# balconyDreams.net
KiCad netlist of a schematic drawn in EAGLE
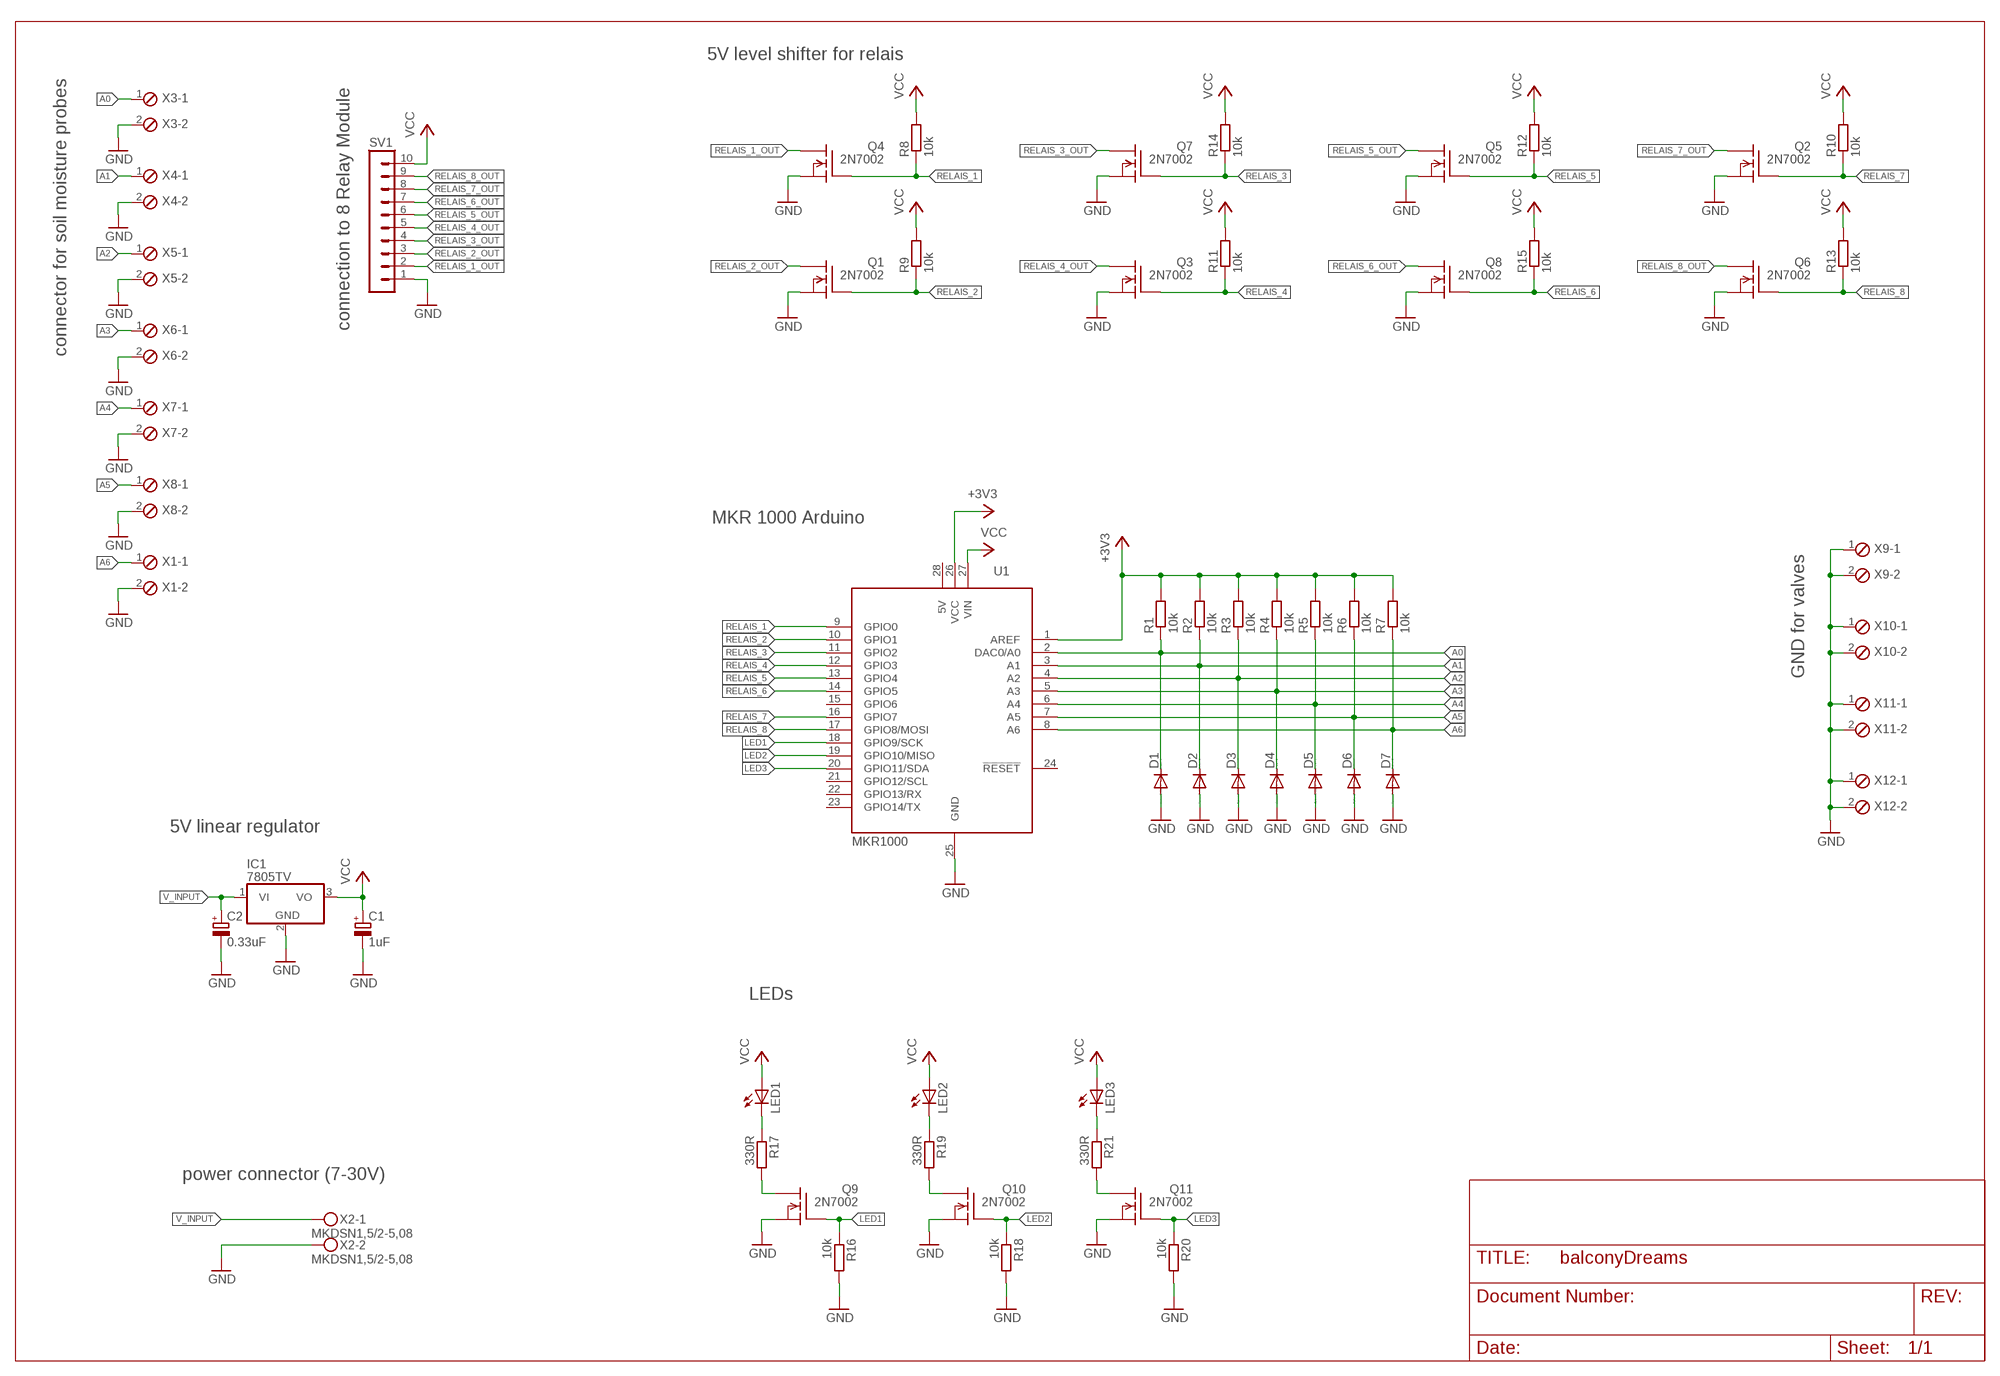
[diagram p0: schematic, sheet 1]

(export (version "E")
  (design (tool "Eeschema 10.0.6"))
  (components
    (comp (ref "C1")
      (value "1uF")
      (footprint "eagle-import:E5-6")
      (libsource (lib "eagle-import") (part "CPOL-EUE5-6"))
    )
    (comp (ref "C2")
      (value "0.33uF")
      (footprint "eagle-import:E5-6")
      (libsource (lib "eagle-import") (part "CPOL-EUE5-6"))
    )
    (comp (ref "D1")
      (value "DIODE-SOD323-W")
      (footprint "eagle-import:SOD323-W")
      (libsource (lib "eagle-import") (part "DIODE-SOD323-W"))
    )
    (comp (ref "D2")
      (value "DIODE-SOD323-W")
      (footprint "eagle-import:SOD323-W")
      (libsource (lib "eagle-import") (part "DIODE-SOD323-W"))
    )
    (comp (ref "D3")
      (value "DIODE-SOD323-W")
      (footprint "eagle-import:SOD323-W")
      (libsource (lib "eagle-import") (part "DIODE-SOD323-W"))
    )
    (comp (ref "D4")
      (value "DIODE-SOD323-W")
      (footprint "eagle-import:SOD323-W")
      (libsource (lib "eagle-import") (part "DIODE-SOD323-W"))
    )
    (comp (ref "D5")
      (value "DIODE-SOD323-W")
      (footprint "eagle-import:SOD323-W")
      (libsource (lib "eagle-import") (part "DIODE-SOD323-W"))
    )
    (comp (ref "D6")
      (value "DIODE-SOD323-W")
      (footprint "eagle-import:SOD323-W")
      (libsource (lib "eagle-import") (part "DIODE-SOD323-W"))
    )
    (comp (ref "D7")
      (value "DIODE-SOD323-W")
      (footprint "eagle-import:SOD323-W")
      (libsource (lib "eagle-import") (part "DIODE-SOD323-W"))
    )
    (comp (ref "IC1")
      (value "7805TV")
      (footprint "eagle-import:TO220V")
      (libsource (lib "eagle-import") (part "78TV05"))
    )
    (comp (ref "LED1")
      (value "LEDCHIPLED_0805")
      (footprint "eagle-import:CHIPLED_0805")
      (libsource (lib "eagle-import") (part "LEDCHIPLED_0805"))
    )
    (comp (ref "LED2")
      (value "LEDCHIPLED_0805")
      (footprint "eagle-import:CHIPLED_0805")
      (libsource (lib "eagle-import") (part "LEDCHIPLED_0805"))
    )
    (comp (ref "LED3")
      (value "LEDCHIPLED_0805")
      (footprint "eagle-import:CHIPLED_0805")
      (libsource (lib "eagle-import") (part "LEDCHIPLED_0805"))
    )
    (comp (ref "Q1")
      (value "2N7002")
      (footprint "eagle-import:SOT23")
      (libsource (lib "eagle-import") (part "2N7002"))
    )
    (comp (ref "Q2")
      (value "2N7002")
      (footprint "eagle-import:SOT23")
      (libsource (lib "eagle-import") (part "2N7002"))
    )
    (comp (ref "Q3")
      (value "2N7002")
      (footprint "eagle-import:SOT23")
      (libsource (lib "eagle-import") (part "2N7002"))
    )
    (comp (ref "Q4")
      (value "2N7002")
      (footprint "eagle-import:SOT23")
      (libsource (lib "eagle-import") (part "2N7002"))
    )
    (comp (ref "Q5")
      (value "2N7002")
      (footprint "eagle-import:SOT23")
      (libsource (lib "eagle-import") (part "2N7002"))
    )
    (comp (ref "Q6")
      (value "2N7002")
      (footprint "eagle-import:SOT23")
      (libsource (lib "eagle-import") (part "2N7002"))
    )
    (comp (ref "Q7")
      (value "2N7002")
      (footprint "eagle-import:SOT23")
      (libsource (lib "eagle-import") (part "2N7002"))
    )
    (comp (ref "Q8")
      (value "2N7002")
      (footprint "eagle-import:SOT23")
      (libsource (lib "eagle-import") (part "2N7002"))
    )
    (comp (ref "Q9")
      (value "2N7002")
      (footprint "eagle-import:SOT23")
      (libsource (lib "eagle-import") (part "2N7002"))
    )
    (comp (ref "Q10")
      (value "2N7002")
      (footprint "eagle-import:SOT23")
      (libsource (lib "eagle-import") (part "2N7002"))
    )
    (comp (ref "Q11")
      (value "2N7002")
      (footprint "eagle-import:SOT23")
      (libsource (lib "eagle-import") (part "2N7002"))
    )
    (comp (ref "R1")
      (value "10k")
      (footprint "eagle-import:R0805")
      (libsource (lib "eagle-import") (part "R-EU_R0805"))
    )
    (comp (ref "R2")
      (value "10k")
      (footprint "eagle-import:R0805")
      (libsource (lib "eagle-import") (part "R-EU_R0805"))
    )
    (comp (ref "R3")
      (value "10k")
      (footprint "eagle-import:R0805")
      (libsource (lib "eagle-import") (part "R-EU_R0805"))
    )
    (comp (ref "R4")
      (value "10k")
      (footprint "eagle-import:R0805")
      (libsource (lib "eagle-import") (part "R-EU_R0805"))
    )
    (comp (ref "R5")
      (value "10k")
      (footprint "eagle-import:R0805")
      (libsource (lib "eagle-import") (part "R-EU_R0805"))
    )
    (comp (ref "R6")
      (value "10k")
      (footprint "eagle-import:R0805")
      (libsource (lib "eagle-import") (part "R-EU_R0805"))
    )
    (comp (ref "R7")
      (value "10k")
      (footprint "eagle-import:R0805")
      (libsource (lib "eagle-import") (part "R-EU_R0805"))
    )
    (comp (ref "R8")
      (value "10k")
      (footprint "eagle-import:R0805")
      (libsource (lib "eagle-import") (part "R-EU_R0805"))
    )
    (comp (ref "R9")
      (value "10k")
      (footprint "eagle-import:R0805")
      (libsource (lib "eagle-import") (part "R-EU_R0805"))
    )
    (comp (ref "R10")
      (value "10k")
      (footprint "eagle-import:R0805")
      (libsource (lib "eagle-import") (part "R-EU_R0805"))
    )
    (comp (ref "R11")
      (value "10k")
      (footprint "eagle-import:R0805")
      (libsource (lib "eagle-import") (part "R-EU_R0805"))
    )
    (comp (ref "R12")
      (value "10k")
      (footprint "eagle-import:R0805")
      (libsource (lib "eagle-import") (part "R-EU_R0805"))
    )
    (comp (ref "R13")
      (value "10k")
      (footprint "eagle-import:R0805")
      (libsource (lib "eagle-import") (part "R-EU_R0805"))
    )
    (comp (ref "R14")
      (value "10k")
      (footprint "eagle-import:R0805")
      (libsource (lib "eagle-import") (part "R-EU_R0805"))
    )
    (comp (ref "R15")
      (value "10k")
      (footprint "eagle-import:R0805")
      (libsource (lib "eagle-import") (part "R-EU_R0805"))
    )
    (comp (ref "R16")
      (value "10k")
      (footprint "eagle-import:R0805")
      (libsource (lib "eagle-import") (part "R-EU_R0805"))
    )
    (comp (ref "R17")
      (value "330R")
      (footprint "eagle-import:R0805")
      (libsource (lib "eagle-import") (part "R-EU_R0805"))
    )
    (comp (ref "R18")
      (value "10k")
      (footprint "eagle-import:R0805")
      (libsource (lib "eagle-import") (part "R-EU_R0805"))
    )
    (comp (ref "R19")
      (value "330R")
      (footprint "eagle-import:R0805")
      (libsource (lib "eagle-import") (part "R-EU_R0805"))
    )
    (comp (ref "R20")
      (value "10k")
      (footprint "eagle-import:R0805")
      (libsource (lib "eagle-import") (part "R-EU_R0805"))
    )
    (comp (ref "R21")
      (value "330R")
      (footprint "eagle-import:R0805")
      (libsource (lib "eagle-import") (part "R-EU_R0805"))
    )
    (comp (ref "SV1")
      (value "MA10-1")
      (footprint "eagle-import:MA10-1")
      (libsource (lib "eagle-import") (part "MA10-1"))
    )
    (comp (ref "U1")
      (value "MKR1000")
      (footprint "eagle-import:MKR1000")
      (libsource (lib "eagle-import") (part "MKR1000"))
    )
    (comp (ref "X1")
      (value "MPT2")
      (footprint "eagle-import:2POL254")
      (libsource (lib "eagle-import") (part "MPT2"))
    )
    (comp (ref "X2")
      (value "MKDSN1,5/2-5,08")
      (footprint "eagle-import:MKDSN1,5_2-5,08")
      (libsource (lib "eagle-import") (part "MKDSN1,5/2-5,08"))
    )
    (comp (ref "X3")
      (value "MPT2")
      (footprint "eagle-import:2POL254")
      (libsource (lib "eagle-import") (part "MPT2"))
    )
    (comp (ref "X4")
      (value "MPT2")
      (footprint "eagle-import:2POL254")
      (libsource (lib "eagle-import") (part "MPT2"))
    )
    (comp (ref "X5")
      (value "MPT2")
      (footprint "eagle-import:2POL254")
      (libsource (lib "eagle-import") (part "MPT2"))
    )
    (comp (ref "X6")
      (value "MPT2")
      (footprint "eagle-import:2POL254")
      (libsource (lib "eagle-import") (part "MPT2"))
    )
    (comp (ref "X7")
      (value "MPT2")
      (footprint "eagle-import:2POL254")
      (libsource (lib "eagle-import") (part "MPT2"))
    )
    (comp (ref "X8")
      (value "MPT2")
      (footprint "eagle-import:2POL254")
      (libsource (lib "eagle-import") (part "MPT2"))
    )
    (comp (ref "X9")
      (value "MPT2")
      (footprint "eagle-import:2POL254")
      (libsource (lib "eagle-import") (part "MPT2"))
    )
    (comp (ref "X10")
      (value "MPT2")
      (footprint "eagle-import:2POL254")
      (libsource (lib "eagle-import") (part "MPT2"))
    )
    (comp (ref "X11")
      (value "MPT2")
      (footprint "eagle-import:2POL254")
      (libsource (lib "eagle-import") (part "MPT2"))
    )
    (comp (ref "X12")
      (value "MPT2")
      (footprint "eagle-import:2POL254")
      (libsource (lib "eagle-import") (part "MPT2"))
    )
  )
  (nets
    (net (code "1") (name "+3V3") (class "Default")
      (node (ref "R1") (pin "2") (pinfunction "2_2") (pintype "passive"))
      (node (ref "R2") (pin "2") (pinfunction "2_2") (pintype "passive"))
      (node (ref "R3") (pin "2") (pinfunction "2_2") (pintype "passive"))
      (node (ref "R4") (pin "2") (pinfunction "2_2") (pintype "passive"))
      (node (ref "R5") (pin "2") (pinfunction "2_2") (pintype "passive"))
      (node (ref "R6") (pin "2") (pinfunction "2_2") (pintype "passive"))
      (node (ref "R7") (pin "2") (pinfunction "2_2") (pintype "passive"))
      (node (ref "U1") (pin "1") (pinfunction "AREF_1") (pintype "bidirectional"))
      (node (ref "U1") (pin "26") (pinfunction "VCC_26") (pintype "bidirectional"))
    )
    (net (code "2") (name "A0") (class "Default")
      (node (ref "D1") (pin "C") (pinfunction "C_C") (pintype "passive"))
      (node (ref "R1") (pin "1") (pinfunction "1_1") (pintype "passive"))
      (node (ref "U1") (pin "2") (pinfunction "DAC0/A0_2") (pintype "bidirectional"))
      (node (ref "X3") (pin "1") (pinfunction "1_1") (pintype "passive"))
    )
    (net (code "3") (name "A1") (class "Default")
      (node (ref "D2") (pin "C") (pinfunction "C_C") (pintype "passive"))
      (node (ref "R2") (pin "1") (pinfunction "1_1") (pintype "passive"))
      (node (ref "U1") (pin "3") (pinfunction "A1_3") (pintype "bidirectional"))
      (node (ref "X4") (pin "1") (pinfunction "1_1") (pintype "passive"))
    )
    (net (code "4") (name "A2") (class "Default")
      (node (ref "D3") (pin "C") (pinfunction "C_C") (pintype "passive"))
      (node (ref "R3") (pin "1") (pinfunction "1_1") (pintype "passive"))
      (node (ref "U1") (pin "4") (pinfunction "A2_4") (pintype "bidirectional"))
      (node (ref "X5") (pin "1") (pinfunction "1_1") (pintype "passive"))
    )
    (net (code "5") (name "A3") (class "Default")
      (node (ref "D4") (pin "C") (pinfunction "C_C") (pintype "passive"))
      (node (ref "R4") (pin "1") (pinfunction "1_1") (pintype "passive"))
      (node (ref "U1") (pin "5") (pinfunction "A3_5") (pintype "bidirectional"))
      (node (ref "X6") (pin "1") (pinfunction "1_1") (pintype "passive"))
    )
    (net (code "6") (name "A4") (class "Default")
      (node (ref "D5") (pin "C") (pinfunction "C_C") (pintype "passive"))
      (node (ref "R5") (pin "1") (pinfunction "1_1") (pintype "passive"))
      (node (ref "U1") (pin "6") (pinfunction "A4_6") (pintype "bidirectional"))
      (node (ref "X7") (pin "1") (pinfunction "1_1") (pintype "passive"))
    )
    (net (code "7") (name "A5") (class "Default")
      (node (ref "D6") (pin "C") (pinfunction "C_C") (pintype "passive"))
      (node (ref "R6") (pin "1") (pinfunction "1_1") (pintype "passive"))
      (node (ref "U1") (pin "7") (pinfunction "A5_7") (pintype "bidirectional"))
      (node (ref "X8") (pin "1") (pinfunction "1_1") (pintype "passive"))
    )
    (net (code "8") (name "A6") (class "Default")
      (node (ref "D7") (pin "C") (pinfunction "C_C") (pintype "passive"))
      (node (ref "R7") (pin "1") (pinfunction "1_1") (pintype "passive"))
      (node (ref "U1") (pin "8") (pinfunction "A6_8") (pintype "bidirectional"))
      (node (ref "X1") (pin "1") (pinfunction "1_1") (pintype "passive"))
    )
    (net (code "9") (name "GND") (class "Default")
      (node (ref "C1") (pin "-") (pinfunction "-_-") (pintype "passive"))
      (node (ref "C2") (pin "-") (pinfunction "-_-") (pintype "passive"))
      (node (ref "D1") (pin "A") (pinfunction "A_A") (pintype "passive"))
      (node (ref "D2") (pin "A") (pinfunction "A_A") (pintype "passive"))
      (node (ref "D3") (pin "A") (pinfunction "A_A") (pintype "passive"))
      (node (ref "D4") (pin "A") (pinfunction "A_A") (pintype "passive"))
      (node (ref "D5") (pin "A") (pinfunction "A_A") (pintype "passive"))
      (node (ref "D6") (pin "A") (pinfunction "A_A") (pintype "passive"))
      (node (ref "D7") (pin "A") (pinfunction "A_A") (pintype "passive"))
      (node (ref "IC1") (pin "2") (pinfunction "GND_2") (pintype "passive"))
      (node (ref "Q1") (pin "2") (pinfunction "S_2") (pintype "passive"))
      (node (ref "Q10") (pin "2") (pinfunction "S_2") (pintype "passive"))
      (node (ref "Q11") (pin "2") (pinfunction "S_2") (pintype "passive"))
      (node (ref "Q2") (pin "2") (pinfunction "S_2") (pintype "passive"))
      (node (ref "Q3") (pin "2") (pinfunction "S_2") (pintype "passive"))
      (node (ref "Q4") (pin "2") (pinfunction "S_2") (pintype "passive"))
      (node (ref "Q5") (pin "2") (pinfunction "S_2") (pintype "passive"))
      (node (ref "Q6") (pin "2") (pinfunction "S_2") (pintype "passive"))
      (node (ref "Q7") (pin "2") (pinfunction "S_2") (pintype "passive"))
      (node (ref "Q8") (pin "2") (pinfunction "S_2") (pintype "passive"))
      (node (ref "Q9") (pin "2") (pinfunction "S_2") (pintype "passive"))
      (node (ref "R16") (pin "2") (pinfunction "2_2") (pintype "passive"))
      (node (ref "R18") (pin "2") (pinfunction "2_2") (pintype "passive"))
      (node (ref "R20") (pin "2") (pinfunction "2_2") (pintype "passive"))
      (node (ref "SV1") (pin "1") (pinfunction "1_1") (pintype "passive"))
      (node (ref "U1") (pin "25") (pinfunction "GND_25") (pintype "bidirectional"))
      (node (ref "X1") (pin "2") (pinfunction "1_2") (pintype "passive"))
      (node (ref "X10") (pin "1") (pinfunction "1_1") (pintype "passive"))
      (node (ref "X10") (pin "2") (pinfunction "1_2") (pintype "passive"))
      (node (ref "X11") (pin "1") (pinfunction "1_1") (pintype "passive"))
      (node (ref "X11") (pin "2") (pinfunction "1_2") (pintype "passive"))
      (node (ref "X12") (pin "1") (pinfunction "1_1") (pintype "passive"))
      (node (ref "X12") (pin "2") (pinfunction "1_2") (pintype "passive"))
      (node (ref "X2") (pin "2") (pinfunction "KL_2") (pintype "passive"))
      (node (ref "X3") (pin "2") (pinfunction "1_2") (pintype "passive"))
      (node (ref "X4") (pin "2") (pinfunction "1_2") (pintype "passive"))
      (node (ref "X5") (pin "2") (pinfunction "1_2") (pintype "passive"))
      (node (ref "X6") (pin "2") (pinfunction "1_2") (pintype "passive"))
      (node (ref "X7") (pin "2") (pinfunction "1_2") (pintype "passive"))
      (node (ref "X8") (pin "2") (pinfunction "1_2") (pintype "passive"))
      (node (ref "X9") (pin "1") (pinfunction "1_1") (pintype "passive"))
      (node (ref "X9") (pin "2") (pinfunction "1_2") (pintype "passive"))
    )
    (net (code "10") (name "LED1") (class "Default")
      (node (ref "Q9") (pin "1") (pinfunction "G_1") (pintype "passive"))
      (node (ref "R16") (pin "1") (pinfunction "1_1") (pintype "passive"))
      (node (ref "U1") (pin "18") (pinfunction "GPIO9/SCK_18") (pintype "bidirectional"))
    )
    (net (code "11") (name "LED2") (class "Default")
      (node (ref "Q10") (pin "1") (pinfunction "G_1") (pintype "passive"))
      (node (ref "R18") (pin "1") (pinfunction "1_1") (pintype "passive"))
      (node (ref "U1") (pin "19") (pinfunction "GPIO10/MISO_19") (pintype "bidirectional"))
    )
    (net (code "12") (name "LED3") (class "Default")
      (node (ref "Q11") (pin "1") (pinfunction "G_1") (pintype "passive"))
      (node (ref "R20") (pin "1") (pinfunction "1_1") (pintype "passive"))
      (node (ref "U1") (pin "20") (pinfunction "GPIO11/SDA_20") (pintype "bidirectional"))
    )
    (net (code "13") (name "Net-(LED1-PadC)") (class "Default")
      (node (ref "LED1") (pin "C") (pinfunction "C_C") (pintype "passive"))
      (node (ref "R17") (pin "1") (pinfunction "1_1") (pintype "passive"))
    )
    (net (code "14") (name "Net-(LED2-PadC)") (class "Default")
      (node (ref "LED2") (pin "C") (pinfunction "C_C") (pintype "passive"))
      (node (ref "R19") (pin "1") (pinfunction "1_1") (pintype "passive"))
    )
    (net (code "15") (name "Net-(LED3-PadC)") (class "Default")
      (node (ref "LED3") (pin "C") (pinfunction "C_C") (pintype "passive"))
      (node (ref "R21") (pin "1") (pinfunction "1_1") (pintype "passive"))
    )
    (net (code "16") (name "Net-(Q9-D)") (class "Default")
      (node (ref "Q9") (pin "3") (pinfunction "D_3") (pintype "passive"))
      (node (ref "R17") (pin "2") (pinfunction "2_2") (pintype "passive"))
    )
    (net (code "17") (name "Net-(Q10-D)") (class "Default")
      (node (ref "Q10") (pin "3") (pinfunction "D_3") (pintype "passive"))
      (node (ref "R19") (pin "2") (pinfunction "2_2") (pintype "passive"))
    )
    (net (code "18") (name "Net-(Q11-D)") (class "Default")
      (node (ref "Q11") (pin "3") (pinfunction "D_3") (pintype "passive"))
      (node (ref "R21") (pin "2") (pinfunction "2_2") (pintype "passive"))
    )
    (net (code "19") (name "RELAIS_1") (class "Default")
      (node (ref "Q4") (pin "1") (pinfunction "G_1") (pintype "passive"))
      (node (ref "R8") (pin "1") (pinfunction "1_1") (pintype "passive"))
      (node (ref "U1") (pin "9") (pinfunction "GPIO0_9") (pintype "bidirectional"))
    )
    (net (code "20") (name "RELAIS_1_OUT") (class "Default")
      (node (ref "Q4") (pin "3") (pinfunction "D_3") (pintype "passive"))
      (node (ref "SV1") (pin "2") (pinfunction "2_2") (pintype "passive"))
    )
    (net (code "21") (name "RELAIS_2") (class "Default")
      (node (ref "Q1") (pin "1") (pinfunction "G_1") (pintype "passive"))
      (node (ref "R9") (pin "1") (pinfunction "1_1") (pintype "passive"))
      (node (ref "U1") (pin "10") (pinfunction "GPIO1_10") (pintype "bidirectional"))
    )
    (net (code "22") (name "RELAIS_2_OUT") (class "Default")
      (node (ref "Q1") (pin "3") (pinfunction "D_3") (pintype "passive"))
      (node (ref "SV1") (pin "3") (pinfunction "3_3") (pintype "passive"))
    )
    (net (code "23") (name "RELAIS_3") (class "Default")
      (node (ref "Q7") (pin "1") (pinfunction "G_1") (pintype "passive"))
      (node (ref "R14") (pin "1") (pinfunction "1_1") (pintype "passive"))
      (node (ref "U1") (pin "11") (pinfunction "GPIO2_11") (pintype "bidirectional"))
    )
    (net (code "24") (name "RELAIS_3_OUT") (class "Default")
      (node (ref "Q7") (pin "3") (pinfunction "D_3") (pintype "passive"))
      (node (ref "SV1") (pin "4") (pinfunction "4_4") (pintype "passive"))
    )
    (net (code "25") (name "RELAIS_4") (class "Default")
      (node (ref "Q3") (pin "1") (pinfunction "G_1") (pintype "passive"))
      (node (ref "R11") (pin "1") (pinfunction "1_1") (pintype "passive"))
      (node (ref "U1") (pin "12") (pinfunction "GPIO3_12") (pintype "bidirectional"))
    )
    (net (code "26") (name "RELAIS_4_OUT") (class "Default")
      (node (ref "Q3") (pin "3") (pinfunction "D_3") (pintype "passive"))
      (node (ref "SV1") (pin "5") (pinfunction "5_5") (pintype "passive"))
    )
    (net (code "27") (name "RELAIS_5") (class "Default")
      (node (ref "Q5") (pin "1") (pinfunction "G_1") (pintype "passive"))
      (node (ref "R12") (pin "1") (pinfunction "1_1") (pintype "passive"))
      (node (ref "U1") (pin "13") (pinfunction "GPIO4_13") (pintype "bidirectional"))
    )
    (net (code "28") (name "RELAIS_5_OUT") (class "Default")
      (node (ref "Q5") (pin "3") (pinfunction "D_3") (pintype "passive"))
      (node (ref "SV1") (pin "6") (pinfunction "6_6") (pintype "passive"))
    )
    (net (code "29") (name "RELAIS_6") (class "Default")
      (node (ref "Q8") (pin "1") (pinfunction "G_1") (pintype "passive"))
      (node (ref "R15") (pin "1") (pinfunction "1_1") (pintype "passive"))
      (node (ref "U1") (pin "14") (pinfunction "GPIO5_14") (pintype "bidirectional"))
    )
    (net (code "30") (name "RELAIS_6_OUT") (class "Default")
      (node (ref "Q8") (pin "3") (pinfunction "D_3") (pintype "passive"))
      (node (ref "SV1") (pin "7") (pinfunction "7_7") (pintype "passive"))
    )
    (net (code "31") (name "RELAIS_7") (class "Default")
      (node (ref "Q2") (pin "1") (pinfunction "G_1") (pintype "passive"))
      (node (ref "R10") (pin "1") (pinfunction "1_1") (pintype "passive"))
      (node (ref "U1") (pin "16") (pinfunction "GPIO7_16") (pintype "bidirectional"))
    )
    (net (code "32") (name "RELAIS_7_OUT") (class "Default")
      (node (ref "Q2") (pin "3") (pinfunction "D_3") (pintype "passive"))
      (node (ref "SV1") (pin "8") (pinfunction "8_8") (pintype "passive"))
    )
    (net (code "33") (name "RELAIS_8") (class "Default")
      (node (ref "Q6") (pin "1") (pinfunction "G_1") (pintype "passive"))
      (node (ref "R13") (pin "1") (pinfunction "1_1") (pintype "passive"))
      (node (ref "U1") (pin "17") (pinfunction "GPIO8/MOSI_17") (pintype "bidirectional"))
    )
    (net (code "34") (name "RELAIS_8_OUT") (class "Default")
      (node (ref "Q6") (pin "3") (pinfunction "D_3") (pintype "passive"))
      (node (ref "SV1") (pin "9") (pinfunction "9_9") (pintype "passive"))
    )
    (net (code "35") (name "VCC") (class "Default")
      (node (ref "C1") (pin "+") (pinfunction "+_+") (pintype "passive"))
      (node (ref "IC1") (pin "3") (pinfunction "VO_3") (pintype "passive"))
      (node (ref "LED1") (pin "A") (pinfunction "A_A") (pintype "passive"))
      (node (ref "LED2") (pin "A") (pinfunction "A_A") (pintype "passive"))
      (node (ref "LED3") (pin "A") (pinfunction "A_A") (pintype "passive"))
      (node (ref "R10") (pin "2") (pinfunction "2_2") (pintype "passive"))
      (node (ref "R11") (pin "2") (pinfunction "2_2") (pintype "passive"))
      (node (ref "R12") (pin "2") (pinfunction "2_2") (pintype "passive"))
      (node (ref "R13") (pin "2") (pinfunction "2_2") (pintype "passive"))
      (node (ref "R14") (pin "2") (pinfunction "2_2") (pintype "passive"))
      (node (ref "R15") (pin "2") (pinfunction "2_2") (pintype "passive"))
      (node (ref "R8") (pin "2") (pinfunction "2_2") (pintype "passive"))
      (node (ref "R9") (pin "2") (pinfunction "2_2") (pintype "passive"))
      (node (ref "SV1") (pin "10") (pinfunction "10_10") (pintype "passive"))
      (node (ref "U1") (pin "27") (pinfunction "VIN_27") (pintype "bidirectional"))
    )
    (net (code "36") (name "V_INPUT") (class "Default")
      (node (ref "C2") (pin "+") (pinfunction "+_+") (pintype "passive"))
      (node (ref "IC1") (pin "1") (pinfunction "VI_1") (pintype "input"))
      (node (ref "X2") (pin "1") (pinfunction "KL_1") (pintype "passive"))
    )
    (net (code "37") (name "unconnected-(U1-5V-Pad28)") (class "Default")
      (node (ref "U1") (pin "28") (pinfunction "5V_28") (pintype "bidirectional"))
    )
    (net (code "38") (name "unconnected-(U1-GPIO6-Pad15)") (class "Default")
      (node (ref "U1") (pin "15") (pinfunction "GPIO6_15") (pintype "bidirectional"))
    )
    (net (code "39") (name "unconnected-(U1-GPIO12{slash}SCL-Pad21)") (class "Default")
      (node (ref "U1") (pin "21") (pinfunction "GPIO12/SCL_21") (pintype "bidirectional"))
    )
    (net (code "40") (name "unconnected-(U1-GPIO13{slash}RX-Pad22)") (class "Default")
      (node (ref "U1") (pin "22") (pinfunction "GPIO13/RX_22") (pintype "bidirectional"))
    )
    (net (code "41") (name "unconnected-(U1-GPIO14{slash}TX-Pad23)") (class "Default")
      (node (ref "U1") (pin "23") (pinfunction "GPIO14/TX_23") (pintype "bidirectional"))
    )
    (net (code "42") (name "unconnected-(U1-~{RESET}-Pad24)") (class "Default")
      (node (ref "U1") (pin "24") (pinfunction "~{RESET}_24") (pintype "bidirectional"))
    )
  )
)
